# Schematic_LLU_PCB_V0_1.net
KiCad netlist of a schematic drawn in EasyEDA
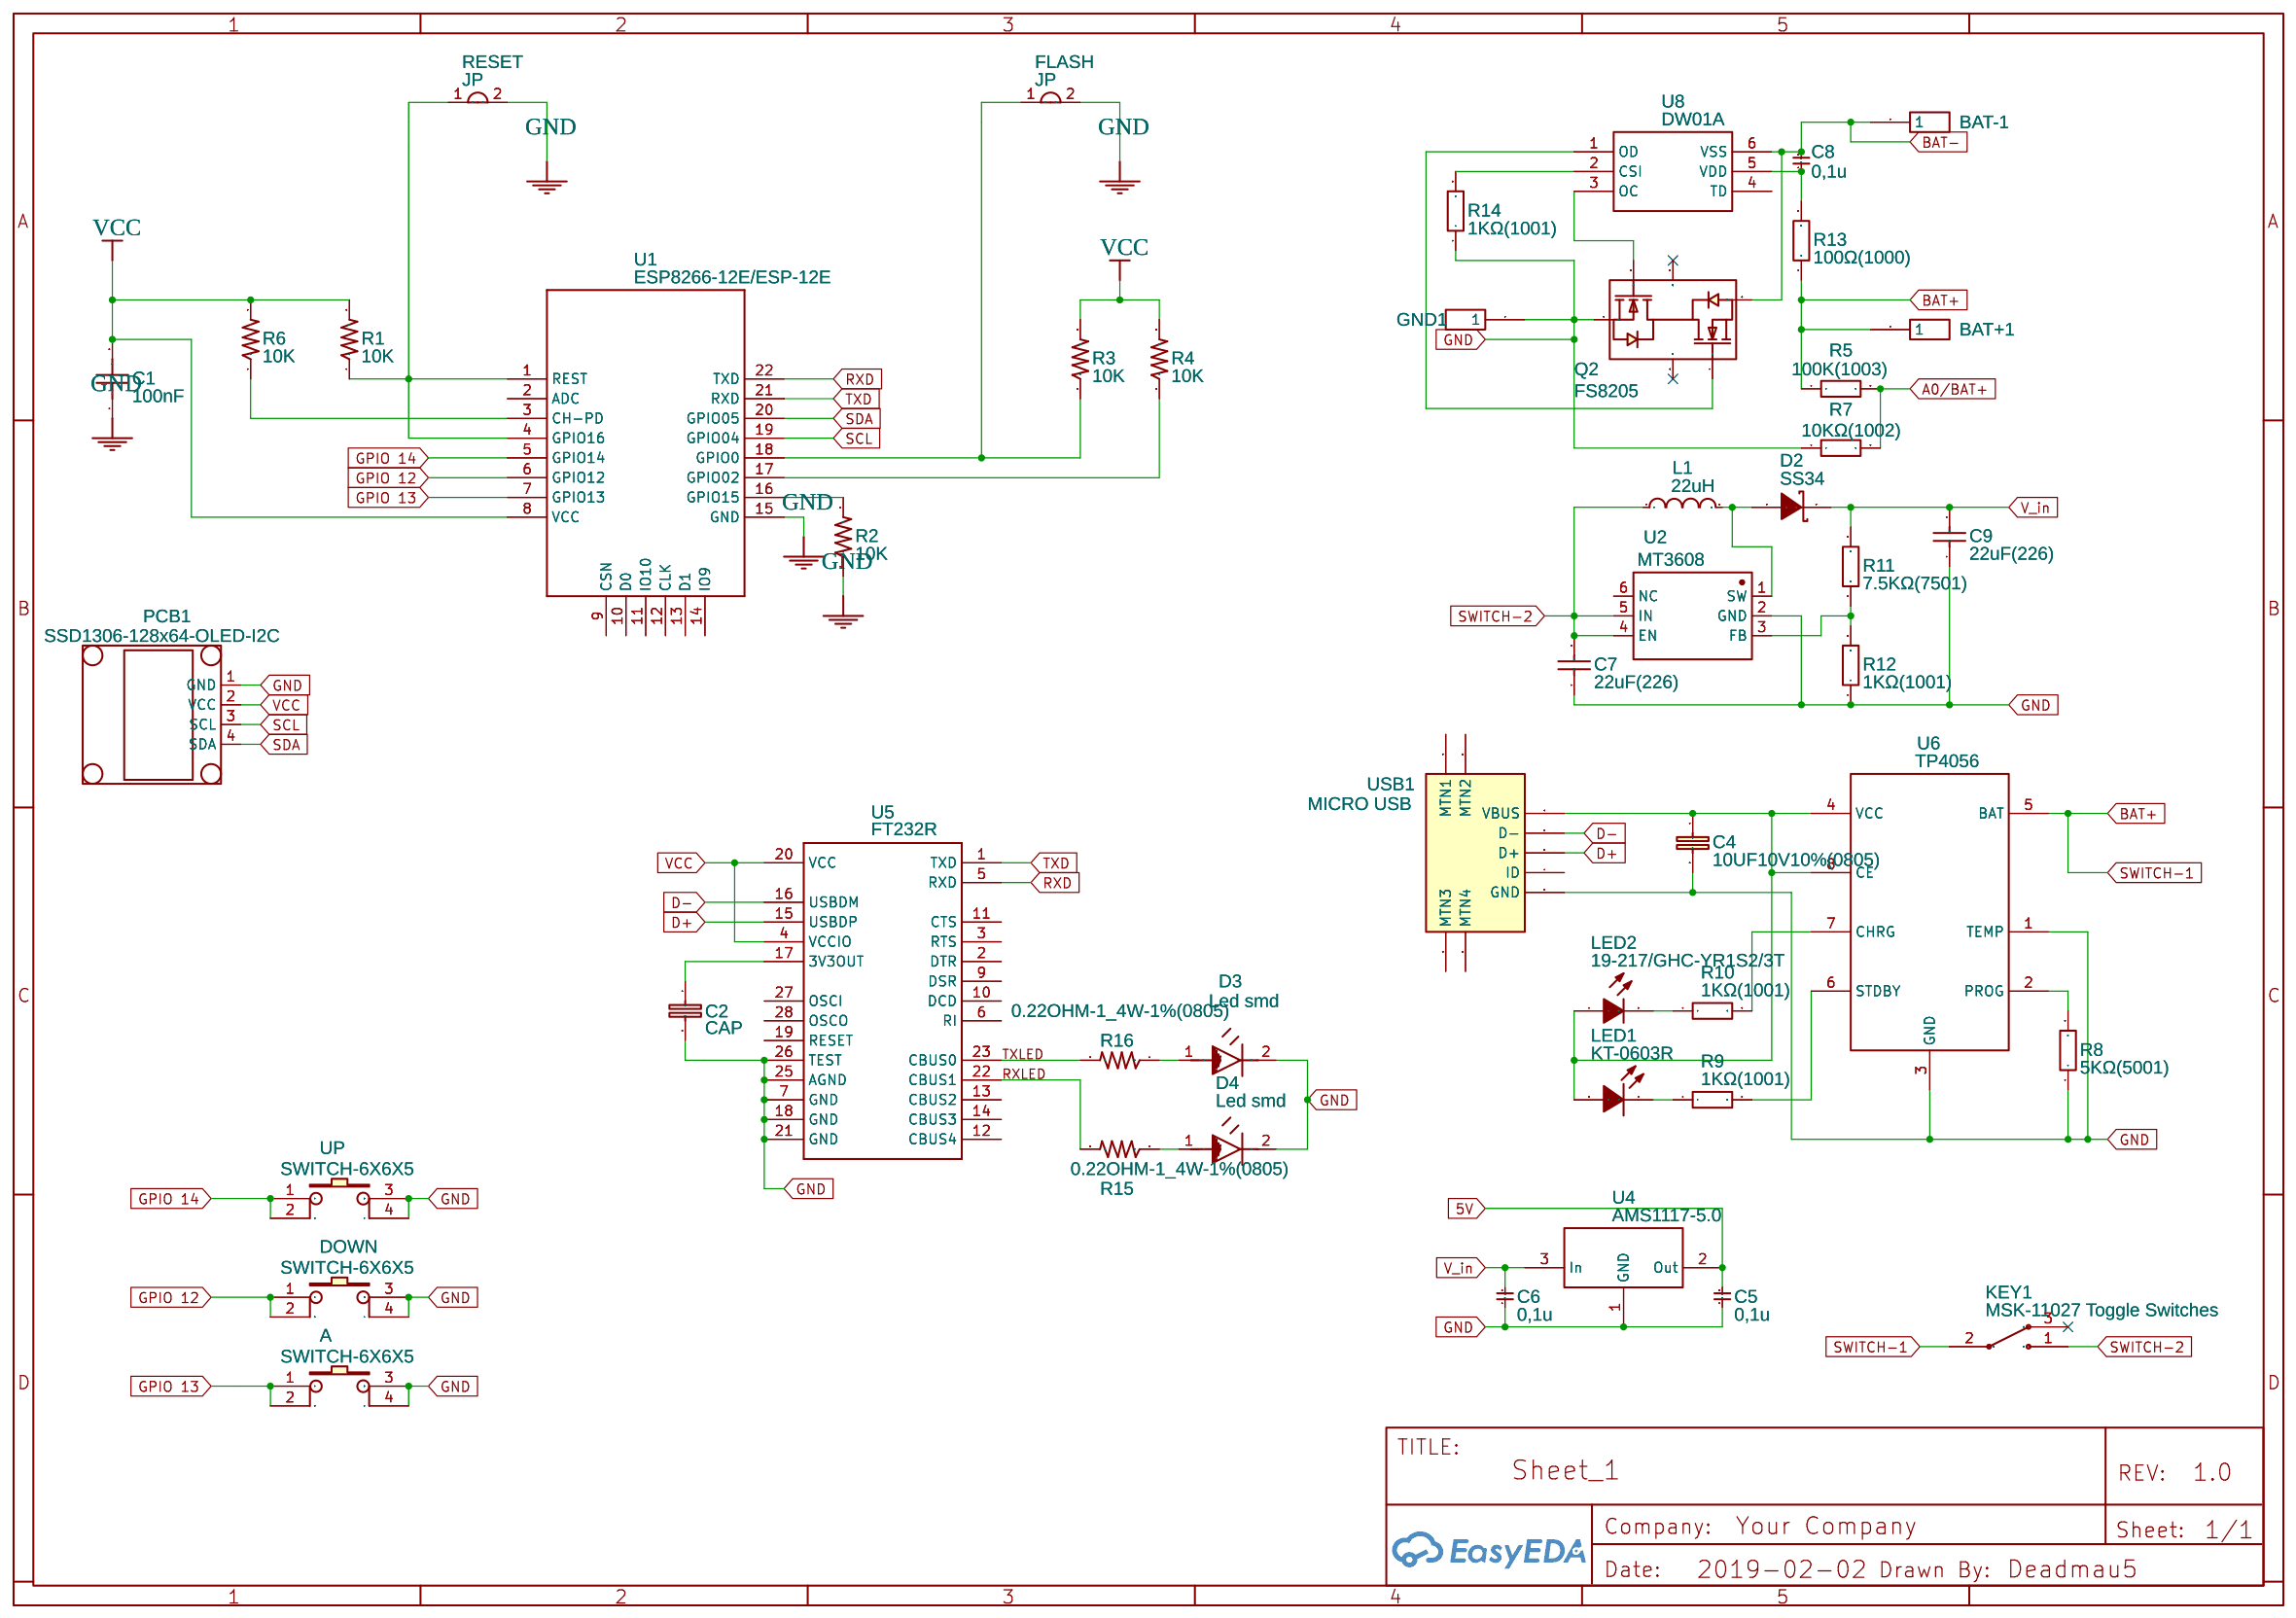
[diagram p0: schematic sheet]

(export (version "E")
  (design (tool "Eeschema 10.0.6"))
  (components
    (comp (ref "A")
      (value "SWITCH-6X6X5")
      (fields
        (field (name "BOM_Manufacturer Part") "SWITCH-6X6X5_TH")
        (field (name "BOM_Supplier Part") "C69330")
      )
      (libsource (lib "") (part "Unknown_160_705"))
    )
    (comp (ref "BAT+1")
      (value "BAT+")
      (fields
        (field (name "BOM_Manufacturer Part") "Header 1*1P")
        (field (name "BOM_Supplier Part") "C81276")
      )
      (libsource (lib "") (part "Unknown_960_160"))
    )
    (comp (ref "BAT-1")
      (value "BAT-")
      (fields
        (field (name "BOM_Manufacturer Part") "Header 1*1P")
        (field (name "BOM_Supplier Part") "C81276")
      )
      (libsource (lib "") (part "Unknown_960_55"))
    )
    (comp (ref "C1")
      (value "100nF")
      (fields
        (field (name "BOM_Manufacturer Part") "GRM2165C1H122JA01D")
        (field (name "BOM_Supplier Part") "C97898")
      )
      (libsource (lib "") (part "Capasitor_0805"))
    )
    (comp (ref "C2")
      (value "CAP")
      (fields (field (name "BOM_Manufacturer Part") "?"))
      (libsource (lib "") (part "Unknown_340_510"))
    )
    (comp (ref "C4")
      (value "10UF10V10%(0805)")
      (fields (field (name "BOM_Manufacturer Part") "?"))
      (libsource (lib "") (part "Unknown_850_425"))
    )
    (comp (ref "C5")
      (value "0,1u")
      (fields
        (field (name "BOM_Manufacturer Part") "0805F106M250NT")
        (field (name "BOM_Supplier Part") "C48181")
      )
      (libsource (lib "") (part "Unknown_865_645"))
    )
    (comp (ref "C6")
      (value "0,1u")
      (fields
        (field (name "BOM_Manufacturer Part") "0805F106M250NT")
        (field (name "BOM_Supplier Part") "C48181")
      )
      (libsource (lib "") (part "Unknown_755_645"))
    )
    (comp (ref "C7")
      (value "22uF(226)")
      (fields
        (field (name "BOM_Manufacturer Part") "0805X226M250NT")
        (field (name "BOM_Supplier Part") "C129303")
      )
      (libsource (lib "") (part "0805X226M250NT"))
    )
    (comp (ref "C8")
      (value "0,1u")
      (fields
        (field (name "BOM_Manufacturer Part") "0805F106M250NT")
        (field (name "BOM_Supplier Part") "C48181")
      )
      (libsource (lib "") (part "Unknown_905_70"))
    )
    (comp (ref "C9")
      (value "22uF(226)")
      (fields
        (field (name "BOM_Manufacturer Part") "0805X226M250NT")
        (field (name "BOM_Supplier Part") "C129303")
      )
      (libsource (lib "") (part "0805X226M250NT"))
    )
    (comp (ref "D2")
      (value "SS34")
      (fields (field (name "BOM_Supplier Part") "C8678"))
      (libsource (lib "") (part "Unknown_900_250"))
    )
    (comp (ref "D3") (value "Led smd") (libsource (lib "") (part "Unknown_590_530")))
    (comp (ref "D4") (value "Led smd") (libsource (lib "") (part "Unknown_590_575")))
    (comp (ref "DOWN")
      (value "SWITCH-6X6X5")
      (fields
        (field (name "BOM_Manufacturer Part") "SWITCH-6X6X5_TH")
        (field (name "BOM_Supplier Part") "C69330")
      )
      (libsource (lib "") (part "Unknown_160_660"))
    )
    (comp (ref "FLASH")
      (value "JP")
      (fields (field (name "BOM_Manufacturer Part") "SMD-Jumper"))
      (libsource (lib "") (part "Unknown_525_45"))
    )
    (comp (ref "GND1")
      (value "GND")
      (fields
        (field (name "BOM_Manufacturer Part") "Header 1*1P")
        (field (name "BOM_Supplier Part") "C81276")
      )
      (libsource (lib "") (part "Unknown_745_155"))
    )
    (comp (ref "KEY1") (value "MSK-11027 Toggle Switches") (libsource (lib "") (part "Unknown_1020_665")))
    (comp (ref "L1")
      (value "22uH")
      (fields
        (field (name "BOM_Manufacturer Part") "SMRH74-220MT")
        (field (name "BOM_Supplier Part") "C27442")
      )
      (libsource (lib "") (part "Unknown_845_250"))
    )
    (comp (ref "LED1")
      (value "KT-0603R")
      (fields (field (name "BOM_Supplier Part") "C2286"))
      (libsource (lib "") (part "Unknown_810_550"))
    )
    (comp (ref "LED2")
      (value "19-217/GHC-YR1S2/3T")
      (fields (field (name "BOM_Supplier Part") "C72043"))
      (libsource (lib "") (part "Unknown_810_505"))
    )
    (comp (ref "PCB1")
      (value "SSD1306-128x64-OLED-I2C")
      (fields (field (name "BOM_Manufacturer Part") "?"))
      (libsource (lib "") (part "Unknown_75_350"))
    )
    (comp (ref "Q2")
      (value "FS8205")
      (fields (field (name "BOM_Supplier Part") "C32254"))
      (libsource (lib "") (part "Unknown_840_155"))
    )
    (comp (ref "R1")
      (value "10K")
      (fields (field (name "BOM_Manufacturer Part") "?"))
      (libsource (lib "") (part "Unknown_170_165"))
    )
    (comp (ref "R2")
      (value "10K")
      (fields (field (name "BOM_Manufacturer Part") "?"))
      (libsource (lib "") (part "Unknown_420_265"))
    )
    (comp (ref "R3")
      (value "10K")
      (fields (field (name "BOM_Manufacturer Part") "?"))
      (libsource (lib "") (part "Unknown_540_175"))
    )
    (comp (ref "R4")
      (value "10K")
      (fields (field (name "BOM_Manufacturer Part") "?"))
      (libsource (lib "") (part "Unknown_580_175"))
    )
    (comp (ref "R5")
      (value "100K(1003)")
      (fields
        (field (name "BOM_Manufacturer Part") "RT0805BRD0710KL")
        (field (name "BOM_Supplier Part") "C110775")
      )
      (libsource (lib "") (part "RT0805BRD0710KL"))
    )
    (comp (ref "R6")
      (value "10K")
      (fields (field (name "BOM_Manufacturer Part") "?"))
      (libsource (lib "") (part "Unknown_120_165"))
    )
    (comp (ref "R7")
      (value "10KΩ(1002)")
      (fields
        (field (name "BOM_Manufacturer Part") "RT0805BRD0710KL")
        (field (name "BOM_Supplier Part") "C110775")
      )
      (libsource (lib "") (part "RT0805BRD0710KL"))
    )
    (comp (ref "R8")
      (value "5KΩ(5001)")
      (fields
        (field (name "BOM_Manufacturer Part") "RT0805BRD075K1L")
        (field (name "BOM_Supplier Part") "C122968")
      )
      (libsource (lib "") (part "RT0805BRD075K1L"))
    )
    (comp (ref "R9")
      (value "1KΩ(1001)")
      (fields
        (field (name "BOM_Manufacturer Part") "RT0805BRD071KL")
        (field (name "BOM_Supplier Part") "C110774")
      )
      (libsource (lib "") (part "RT0805BRD071KL"))
    )
    (comp (ref "R10")
      (value "1KΩ(1001)")
      (fields
        (field (name "BOM_Manufacturer Part") "RT0805BRD071KL")
        (field (name "BOM_Supplier Part") "C110774")
      )
      (libsource (lib "") (part "RT0805BRD071KL"))
    )
    (comp (ref "R11")
      (value "7.5KΩ(7501)")
      (fields
        (field (name "BOM_Manufacturer Part") "RC0805FR-077K5L")
        (field (name "BOM_Supplier Part") "C114547")
      )
      (libsource (lib "") (part "RC0805FR-077K5L"))
    )
    (comp (ref "R12")
      (value "1KΩ(1001)")
      (fields
        (field (name "BOM_Manufacturer Part") "RT0805BRD071KL")
        (field (name "BOM_Supplier Part") "C110774")
      )
      (libsource (lib "") (part "RT0805BRD071KL_1"))
    )
    (comp (ref "R13")
      (value "100Ω(1000)")
      (fields
        (field (name "BOM_Manufacturer Part") "CR0805F81000G")
        (field (name "BOM_Supplier Part") "C101403")
      )
      (libsource (lib "") (part "CR0805F81000G"))
    )
    (comp (ref "R14")
      (value "1KΩ(1001)")
      (fields
        (field (name "BOM_Manufacturer Part") "RTT051001FTP")
        (field (name "BOM_Supplier Part") "C103903")
      )
      (libsource (lib "") (part "RTT051001FTP"))
    )
    (comp (ref "R15")
      (value "0.22OHM-1_4W-1%(0805)")
      (fields (field (name "BOM_Manufacturer Part") "?"))
      (libsource (lib "") (part "Unknown_560_575"))
    )
    (comp (ref "R16")
      (value "0.22OHM-1_4W-1%(0805)")
      (fields (field (name "BOM_Manufacturer Part") "?"))
      (libsource (lib "") (part "Unknown_560_530"))
    )
    (comp (ref "RESET")
      (value "JP")
      (fields (field (name "BOM_Manufacturer Part") "SMD-Jumper"))
      (libsource (lib "") (part "Unknown_235_45"))
    )
    (comp (ref "U1")
      (value "ESP8266-12E/ESP-12E")
      (fields (field (name "BOM_Supplier Part") "317060015"))
      (libsource (lib "") (part "Unknown_320_235"))
    )
    (comp (ref "U2")
      (value "MT3608")
      (fields (field (name "BOM_Supplier Part") "C84817"))
      (libsource (lib "") (part "Unknown_860_285"))
    )
    (comp (ref "U4")
      (value "AMS1117-5.0")
      (fields (field (name "BOM_Supplier Part") "C6187"))
      (libsource (lib "") (part "Unknown_815_635"))
    )
    (comp (ref "U5")
      (value "FT232R")
      (fields (field (name "BOM_Manufacturer Part") "?"))
      (libsource (lib "") (part "Unknown_440_500"))
    )
    (comp (ref "U6")
      (value "TP4056")
      (fields (field (name "BOM_Supplier Part") "C16581"))
      (libsource (lib "") (part "Unknown_970_465"))
    )
    (comp (ref "U8")
      (value "DW01A")
      (fields (field (name "BOM_Supplier Part") "C85680"))
      (libsource (lib "") (part "Unknown_840_80"))
    )
    (comp (ref "UP")
      (value "SWITCH-6X6X5")
      (fields
        (field (name "BOM_Manufacturer Part") "SWITCH-6X6X5_TH")
        (field (name "BOM_Supplier Part") "C69330")
      )
      (libsource (lib "") (part "Unknown_160_610"))
    )
    (comp (ref "USB1")
      (value "MICRO USB")
      (fields
        (field (name "BOM_Manufacturer Part") "MICRO USB 5S B")
        (field (name "BOM_Supplier Part") "C10418")
      )
      (libsource (lib "") (part "Unknown_735_425"))
    )
  )
  (nets
    (net (code "1") (name "5V") (class "Default")
      (node (ref "C5") (pin "2") (pinfunction "2_2") (pintype "input"))
      (node (ref "U4") (pin "2") (pinfunction "Out_2") (pintype "unspecified"))
    )
    (net (code "2") (name "A0{slash}BAT+") (class "Default")
      (node (ref "R5") (pin "2") (pinfunction "2_2") (pintype "input"))
      (node (ref "R7") (pin "2") (pinfunction "2_2") (pintype "input"))
    )
    (net (code "3") (name "BAT+") (class "Default")
      (node (ref "BAT+1") (pin "1") (pinfunction "1_1") (pintype "input"))
      (node (ref "KEY1") (pin "2") (pinfunction "2_2") (pintype "unspecified"))
      (node (ref "R13") (pin "1") (pinfunction "1_1") (pintype "input"))
      (node (ref "R5") (pin "1") (pinfunction "1_1") (pintype "input"))
      (node (ref "U6") (pin "5") (pinfunction "BAT_5") (pintype "unspecified"))
    )
    (net (code "4") (name "BAT-") (class "Default")
      (node (ref "BAT-1") (pin "1") (pinfunction "1_1") (pintype "input"))
      (node (ref "C8") (pin "2") (pinfunction "2_2") (pintype "input"))
      (node (ref "Q2") (pin "3") (pinfunction "S2_3") (pintype "unspecified"))
      (node (ref "U8") (pin "6") (pinfunction "VSS_6") (pintype "unspecified"))
    )
    (net (code "5") (name "D+") (class "Default")
      (node (ref "U5") (pin "15") (pinfunction "USBDP_15") (pintype "unspecified"))
      (node (ref "USB1") (pin "3") (pinfunction "D+_3") (pintype "input"))
    )
    (net (code "6") (name "D-") (class "Default")
      (node (ref "U5") (pin "16") (pinfunction "USBDM_16") (pintype "unspecified"))
      (node (ref "USB1") (pin "2") (pinfunction "D-_2") (pintype "input"))
    )
    (net (code "7") (name "GND") (class "Default")
      (node (ref "A") (pin "3") (pinfunction "3_3") (pintype "input"))
      (node (ref "A") (pin "4") (pinfunction "4_4") (pintype "input"))
      (node (ref "C1") (pin "1") (pinfunction "1_1") (pintype "unspecified"))
      (node (ref "C2") (pin "2") (pinfunction "2_2") (pintype "unspecified"))
      (node (ref "C4") (pin "2") (pinfunction "2_2") (pintype "unspecified"))
      (node (ref "C5") (pin "1") (pinfunction "1_1") (pintype "input"))
      (node (ref "C6") (pin "1") (pinfunction "1_1") (pintype "input"))
      (node (ref "C7") (pin "1") (pinfunction "1_1") (pintype "input"))
      (node (ref "C9") (pin "1") (pinfunction "1_1") (pintype "input"))
      (node (ref "D3") (pin "2") (pinfunction "2_2") (pintype "unspecified"))
      (node (ref "D4") (pin "2") (pinfunction "2_2") (pintype "unspecified"))
      (node (ref "DOWN") (pin "3") (pinfunction "3_3") (pintype "input"))
      (node (ref "DOWN") (pin "4") (pinfunction "4_4") (pintype "input"))
      (node (ref "FLASH") (pin "2") (pinfunction "2_2") (pintype "unspecified"))
      (node (ref "GND1") (pin "1") (pinfunction "1_1") (pintype "input"))
      (node (ref "PCB1") (pin "1") (pinfunction "GND_1") (pintype "input"))
      (node (ref "Q2") (pin "1") (pinfunction "S1_1") (pintype "unspecified"))
      (node (ref "R12") (pin "1") (pinfunction "1_1") (pintype "input"))
      (node (ref "R14") (pin "1") (pinfunction "1_1") (pintype "input"))
      (node (ref "R2") (pin "1") (pinfunction "1_1") (pintype "unspecified"))
      (node (ref "R7") (pin "1") (pinfunction "1_1") (pintype "input"))
      (node (ref "R8") (pin "1") (pinfunction "1_1") (pintype "input"))
      (node (ref "RESET") (pin "2") (pinfunction "2_2") (pintype "unspecified"))
      (node (ref "U1") (pin "15") (pinfunction "GND_15") (pintype "unspecified"))
      (node (ref "U2") (pin "2") (pinfunction "GND_2") (pintype "unspecified"))
      (node (ref "U4") (pin "1") (pinfunction "GND_1") (pintype "unspecified"))
      (node (ref "U5") (pin "18") (pinfunction "GND_18") (pintype "passive"))
      (node (ref "U5") (pin "21") (pinfunction "GND_21") (pintype "passive"))
      (node (ref "U5") (pin "25") (pinfunction "AGND_25") (pintype "passive"))
      (node (ref "U5") (pin "26") (pinfunction "TEST_26") (pintype "input"))
      (node (ref "U5") (pin "7") (pinfunction "GND_7") (pintype "passive"))
      (node (ref "U6") (pin "1") (pinfunction "TEMP_1") (pintype "unspecified"))
      (node (ref "U6") (pin "3") (pinfunction "GND_3") (pintype "unspecified"))
      (node (ref "UP") (pin "3") (pinfunction "3_3") (pintype "input"))
      (node (ref "UP") (pin "4") (pinfunction "4_4") (pintype "input"))
      (node (ref "USB1") (pin "5") (pinfunction "GND_5") (pintype "input"))
    )
    (net (code "8") (name "GPIO 12") (class "Default")
      (node (ref "DOWN") (pin "1") (pinfunction "1_1") (pintype "input"))
      (node (ref "DOWN") (pin "2") (pinfunction "2_2") (pintype "input"))
      (node (ref "U1") (pin "6") (pinfunction "GPIO12_6") (pintype "unspecified"))
    )
    (net (code "9") (name "GPIO 13") (class "Default")
      (node (ref "A") (pin "1") (pinfunction "1_1") (pintype "input"))
      (node (ref "A") (pin "2") (pinfunction "2_2") (pintype "input"))
      (node (ref "U1") (pin "7") (pinfunction "GPIO13_7") (pintype "unspecified"))
    )
    (net (code "10") (name "GPIO 14") (class "Default")
      (node (ref "U1") (pin "5") (pinfunction "GPIO14_5") (pintype "unspecified"))
      (node (ref "UP") (pin "1") (pinfunction "1_1") (pintype "input"))
      (node (ref "UP") (pin "2") (pinfunction "2_2") (pintype "input"))
    )
    (net (code "11") (name "Net-(D2-A)") (class "Default")
      (node (ref "D2") (pin "1") (pinfunction "A_1") (pintype "unspecified"))
      (node (ref "L1") (pin "2") (pinfunction "2_2") (pintype "unspecified"))
      (node (ref "U2") (pin "1") (pinfunction "SW_1") (pintype "unspecified"))
    )
    (net (code "12") (name "Net-(D3-Pad1)") (class "Default")
      (node (ref "D3") (pin "1") (pinfunction "1_1") (pintype "unspecified"))
      (node (ref "R16") (pin "1") (pinfunction "1_1") (pintype "unspecified"))
    )
    (net (code "13") (name "Net-(D4-Pad1)") (class "Default")
      (node (ref "D4") (pin "1") (pinfunction "1_1") (pintype "unspecified"))
      (node (ref "R15") (pin "1") (pinfunction "1_1") (pintype "unspecified"))
    )
    (net (code "14") (name "Net-(LED1-A)") (class "Default")
      (node (ref "C4") (pin "1") (pinfunction "1_1") (pintype "unspecified"))
      (node (ref "LED1") (pin "2") (pinfunction "A_2") (pintype "unspecified"))
      (node (ref "LED2") (pin "1") (pinfunction "A_1") (pintype "input"))
      (node (ref "U6") (pin "4") (pinfunction "VCC_4") (pintype "unspecified"))
      (node (ref "U6") (pin "8") (pinfunction "CE_8") (pintype "unspecified"))
      (node (ref "USB1") (pin "1") (pinfunction "VBUS_1") (pintype "input"))
    )
    (net (code "15") (name "Net-(LED1-K)") (class "Default")
      (node (ref "LED1") (pin "1") (pinfunction "K_1") (pintype "unspecified"))
      (node (ref "R9") (pin "1") (pinfunction "1_1") (pintype "input"))
    )
    (net (code "16") (name "Net-(LED2-C)") (class "Default")
      (node (ref "LED2") (pin "2") (pinfunction "C_2") (pintype "input"))
      (node (ref "R10") (pin "1") (pinfunction "1_1") (pintype "input"))
    )
    (net (code "17") (name "Net-(Q2-G1)") (class "Default")
      (node (ref "Q2") (pin "6") (pinfunction "G1_6") (pintype "unspecified"))
      (node (ref "U8") (pin "3") (pinfunction "OC_3") (pintype "unspecified"))
    )
    (net (code "18") (name "Net-(Q2-G2)") (class "Default")
      (node (ref "Q2") (pin "4") (pinfunction "G2_4") (pintype "unspecified"))
      (node (ref "U8") (pin "1") (pinfunction "OD_1") (pintype "unspecified"))
    )
    (net (code "19") (name "Net-(U1-CH-PD)") (class "Default")
      (node (ref "R6") (pin "1") (pinfunction "1_1") (pintype "unspecified"))
      (node (ref "U1") (pin "3") (pinfunction "CH-PD_3") (pintype "unspecified"))
    )
    (net (code "20") (name "Net-(U1-GPIO0)") (class "Default")
      (node (ref "FLASH") (pin "1") (pinfunction "1_1") (pintype "unspecified"))
      (node (ref "R3") (pin "1") (pinfunction "1_1") (pintype "unspecified"))
      (node (ref "U1") (pin "18") (pinfunction "GPIO0_18") (pintype "unspecified"))
    )
    (net (code "21") (name "Net-(U1-GPIO02)") (class "Default")
      (node (ref "R4") (pin "1") (pinfunction "1_1") (pintype "unspecified"))
      (node (ref "U1") (pin "17") (pinfunction "GPIO02_17") (pintype "unspecified"))
    )
    (net (code "22") (name "Net-(U1-GPIO15)") (class "Default")
      (node (ref "R2") (pin "2") (pinfunction "2_2") (pintype "unspecified"))
      (node (ref "U1") (pin "16") (pinfunction "GPIO15_16") (pintype "unspecified"))
    )
    (net (code "23") (name "Net-(U1-GPIO16)") (class "Default")
      (node (ref "R1") (pin "1") (pinfunction "1_1") (pintype "unspecified"))
      (node (ref "RESET") (pin "1") (pinfunction "1_1") (pintype "unspecified"))
      (node (ref "U1") (pin "1") (pinfunction "REST_1") (pintype "unspecified"))
      (node (ref "U1") (pin "4") (pinfunction "GPIO16_4") (pintype "unspecified"))
    )
    (net (code "24") (name "Net-(U2-FB)") (class "Default")
      (node (ref "R11") (pin "1") (pinfunction "1_1") (pintype "input"))
      (node (ref "R12") (pin "2") (pinfunction "2_2") (pintype "input"))
      (node (ref "U2") (pin "3") (pinfunction "FB_3") (pintype "unspecified"))
    )
    (net (code "25") (name "Net-(U5-3V3OUT)") (class "Default")
      (node (ref "C2") (pin "1") (pinfunction "1_1") (pintype "unspecified"))
      (node (ref "U5") (pin "17") (pinfunction "3V3OUT_17") (pintype "output"))
    )
    (net (code "26") (name "Net-(U5-CBUS0)") (class "Default")
      (node (ref "R16") (pin "2") (pinfunction "2_2") (pintype "unspecified"))
      (node (ref "U5") (pin "23") (pinfunction "CBUS0_23") (pintype "input"))
    )
    (net (code "27") (name "Net-(U5-CBUS1)") (class "Default")
      (node (ref "R15") (pin "2") (pinfunction "2_2") (pintype "unspecified"))
      (node (ref "U5") (pin "22") (pinfunction "CBUS1_22") (pintype "input"))
    )
    (net (code "28") (name "Net-(U6-CHRG)") (class "Default")
      (node (ref "R10") (pin "2") (pinfunction "2_2") (pintype "input"))
      (node (ref "U6") (pin "7") (pinfunction "CHRG_7") (pintype "unspecified"))
    )
    (net (code "29") (name "Net-(U6-PROG)") (class "Default")
      (node (ref "R8") (pin "2") (pinfunction "2_2") (pintype "input"))
      (node (ref "U6") (pin "2") (pinfunction "PROG_2") (pintype "unspecified"))
    )
    (net (code "30") (name "Net-(U6-STDBY)") (class "Default")
      (node (ref "R9") (pin "2") (pinfunction "2_2") (pintype "input"))
      (node (ref "U6") (pin "6") (pinfunction "STDBY_6") (pintype "unspecified"))
    )
    (net (code "31") (name "Net-(U8-CSI)") (class "Default")
      (node (ref "R14") (pin "2") (pinfunction "2_2") (pintype "input"))
      (node (ref "U8") (pin "2") (pinfunction "CSI_2") (pintype "unspecified"))
    )
    (net (code "32") (name "Net-(U8-VDD)") (class "Default")
      (node (ref "C8") (pin "1") (pinfunction "1_1") (pintype "input"))
      (node (ref "R13") (pin "2") (pinfunction "2_2") (pintype "input"))
      (node (ref "U8") (pin "5") (pinfunction "VDD_5") (pintype "unspecified"))
    )
    (net (code "33") (name "RXD") (class "Default")
      (node (ref "U1") (pin "22") (pinfunction "TXD_22") (pintype "unspecified"))
      (node (ref "U5") (pin "5") (pinfunction "RXD_5") (pintype "input"))
    )
    (net (code "34") (name "SCL") (class "Default")
      (node (ref "PCB1") (pin "3") (pinfunction "SCL_3") (pintype "passive"))
      (node (ref "U1") (pin "19") (pinfunction "GPIO04_19") (pintype "unspecified"))
    )
    (net (code "35") (name "SDA") (class "Default")
      (node (ref "PCB1") (pin "4") (pinfunction "SDA_4") (pintype "passive"))
      (node (ref "U1") (pin "20") (pinfunction "GPIO05_20") (pintype "unspecified"))
    )
    (net (code "36") (name "SWITCH-2") (class "Default")
      (node (ref "C7") (pin "2") (pinfunction "2_2") (pintype "input"))
      (node (ref "KEY1") (pin "1") (pinfunction "1_1") (pintype "unspecified"))
      (node (ref "L1") (pin "1") (pinfunction "1_1") (pintype "unspecified"))
      (node (ref "U2") (pin "4") (pinfunction "EN_4") (pintype "unspecified"))
      (node (ref "U2") (pin "5") (pinfunction "IN_5") (pintype "unspecified"))
    )
    (net (code "37") (name "TXD") (class "Default")
      (node (ref "U1") (pin "21") (pinfunction "RXD_21") (pintype "unspecified"))
      (node (ref "U5") (pin "1") (pinfunction "TXD_1") (pintype "output"))
    )
    (net (code "38") (name "VCC") (class "Default")
      (node (ref "C1") (pin "2") (pinfunction "2_2") (pintype "unspecified"))
      (node (ref "PCB1") (pin "2") (pinfunction "VCC_2") (pintype "input"))
      (node (ref "R1") (pin "2") (pinfunction "2_2") (pintype "unspecified"))
      (node (ref "R3") (pin "2") (pinfunction "2_2") (pintype "unspecified"))
      (node (ref "R4") (pin "2") (pinfunction "2_2") (pintype "unspecified"))
      (node (ref "R6") (pin "2") (pinfunction "2_2") (pintype "unspecified"))
      (node (ref "U1") (pin "8") (pinfunction "VCC_8") (pintype "unspecified"))
      (node (ref "U5") (pin "20") (pinfunction "VCC_20") (pintype "passive"))
      (node (ref "U5") (pin "4") (pinfunction "VCCIO_4") (pintype "passive"))
    )
    (net (code "39") (name "V_in") (class "Default")
      (node (ref "C6") (pin "2") (pinfunction "2_2") (pintype "input"))
      (node (ref "C9") (pin "2") (pinfunction "2_2") (pintype "input"))
      (node (ref "D2") (pin "2") (pinfunction "K_2") (pintype "unspecified"))
      (node (ref "R11") (pin "2") (pinfunction "2_2") (pintype "input"))
      (node (ref "U4") (pin "3") (pinfunction "In_3") (pintype "unspecified"))
    )
    (net (code "40") (name "unconnected-(KEY1-Pad3)") (class "Default")
      (node (ref "KEY1") (pin "3") (pinfunction "3_3") (pintype "unspecified+no_connect"))
    )
    (net (code "41") (name "unconnected-(Q2-D12-Pad2)") (class "Default")
      (node (ref "Q2") (pin "2") (pinfunction "D12_2") (pintype "unspecified+no_connect"))
    )
    (net (code "42") (name "unconnected-(Q2-D12-Pad5)") (class "Default")
      (node (ref "Q2") (pin "5") (pinfunction "D12_5") (pintype "unspecified+no_connect"))
    )
    (net (code "43") (name "unconnected-(U1-ADC-Pad2)") (class "Default")
      (node (ref "U1") (pin "2") (pinfunction "ADC_2") (pintype "unspecified"))
    )
    (net (code "44") (name "unconnected-(U1-CLK-Pad12)") (class "Default")
      (node (ref "U1") (pin "12") (pinfunction "CLK_12") (pintype "unspecified"))
    )
    (net (code "45") (name "unconnected-(U1-CSN-Pad9)") (class "Default")
      (node (ref "U1") (pin "9") (pinfunction "CSN_9") (pintype "unspecified"))
    )
    (net (code "46") (name "unconnected-(U1-D0-Pad10)") (class "Default")
      (node (ref "U1") (pin "10") (pinfunction "D0_10") (pintype "unspecified"))
    )
    (net (code "47") (name "unconnected-(U1-D1-Pad13)") (class "Default")
      (node (ref "U1") (pin "13") (pinfunction "D1_13") (pintype "unspecified"))
    )
    (net (code "48") (name "unconnected-(U1-IO9-Pad14)") (class "Default")
      (node (ref "U1") (pin "14") (pinfunction "IO9_14") (pintype "unspecified"))
    )
    (net (code "49") (name "unconnected-(U1-IO10-Pad11)") (class "Default")
      (node (ref "U1") (pin "11") (pinfunction "IO10_11") (pintype "unspecified"))
    )
    (net (code "50") (name "unconnected-(U2-NC-Pad6)") (class "Default")
      (node (ref "U2") (pin "6") (pinfunction "NC_6") (pintype "unspecified"))
    )
    (net (code "51") (name "unconnected-(U5-CBUS2-Pad13)") (class "Default")
      (node (ref "U5") (pin "13") (pinfunction "CBUS2_13") (pintype "input"))
    )
    (net (code "52") (name "unconnected-(U5-CBUS3-Pad14)") (class "Default")
      (node (ref "U5") (pin "14") (pinfunction "CBUS3_14") (pintype "input"))
    )
    (net (code "53") (name "unconnected-(U5-CBUS4-Pad12)") (class "Default")
      (node (ref "U5") (pin "12") (pinfunction "CBUS4_12") (pintype "input"))
    )
    (net (code "54") (name "unconnected-(U5-CTS-Pad11)") (class "Default")
      (node (ref "U5") (pin "11") (pinfunction "CTS_11") (pintype "input"))
    )
    (net (code "55") (name "unconnected-(U5-DCD-Pad10)") (class "Default")
      (node (ref "U5") (pin "10") (pinfunction "DCD_10") (pintype "input"))
    )
    (net (code "56") (name "unconnected-(U5-DSR-Pad9)") (class "Default")
      (node (ref "U5") (pin "9") (pinfunction "DSR_9") (pintype "input"))
    )
    (net (code "57") (name "unconnected-(U5-DTR-Pad2)") (class "Default")
      (node (ref "U5") (pin "2") (pinfunction "DTR_2") (pintype "output"))
    )
    (net (code "58") (name "unconnected-(U5-OSCI-Pad27)") (class "Default")
      (node (ref "U5") (pin "27") (pinfunction "OSCI_27") (pintype "input"))
    )
    (net (code "59") (name "unconnected-(U5-OSCO-Pad28)") (class "Default")
      (node (ref "U5") (pin "28") (pinfunction "OSCO_28") (pintype "output"))
    )
    (net (code "60") (name "unconnected-(U5-RESET-Pad19)") (class "Default")
      (node (ref "U5") (pin "19") (pinfunction "RESET_19") (pintype "input"))
    )
    (net (code "61") (name "unconnected-(U5-RI-Pad6)") (class "Default")
      (node (ref "U5") (pin "6") (pinfunction "RI_6") (pintype "input"))
    )
    (net (code "62") (name "unconnected-(U5-RTS-Pad3)") (class "Default")
      (node (ref "U5") (pin "3") (pinfunction "RTS_3") (pintype "output"))
    )
    (net (code "63") (name "unconnected-(U8-TD-Pad4)") (class "Default")
      (node (ref "U8") (pin "4") (pinfunction "TD_4") (pintype "unspecified"))
    )
    (net (code "64") (name "unconnected-(USB1-ID-Pad4)") (class "Default")
      (node (ref "USB1") (pin "4") (pinfunction "ID_4") (pintype "input"))
    )
    (net (code "65") (name "unconnected-(USB1-MTN1-Pad0)") (class "Default")
      (node (ref "USB1") (pin "0") (pinfunction "MTN1_0") (pintype "input"))
    )
    (net (code "66") (name "unconnected-(USB1-MTN2-Pad0)") (class "Default")
      (node (ref "USB1") (pin "0") (pinfunction "MTN2_0") (pintype "input"))
    )
    (net (code "67") (name "unconnected-(USB1-MTN3-Pad0)") (class "Default")
      (node (ref "USB1") (pin "0") (pinfunction "MTN3_0") (pintype "input"))
    )
    (net (code "68") (name "unconnected-(USB1-MTN4-Pad0)") (class "Default")
      (node (ref "USB1") (pin "0") (pinfunction "MTN4_0") (pintype "input"))
    )
  )
)
